# 05_INPUT.net
KiCad netlist of a schematic drawn in Altium Designer
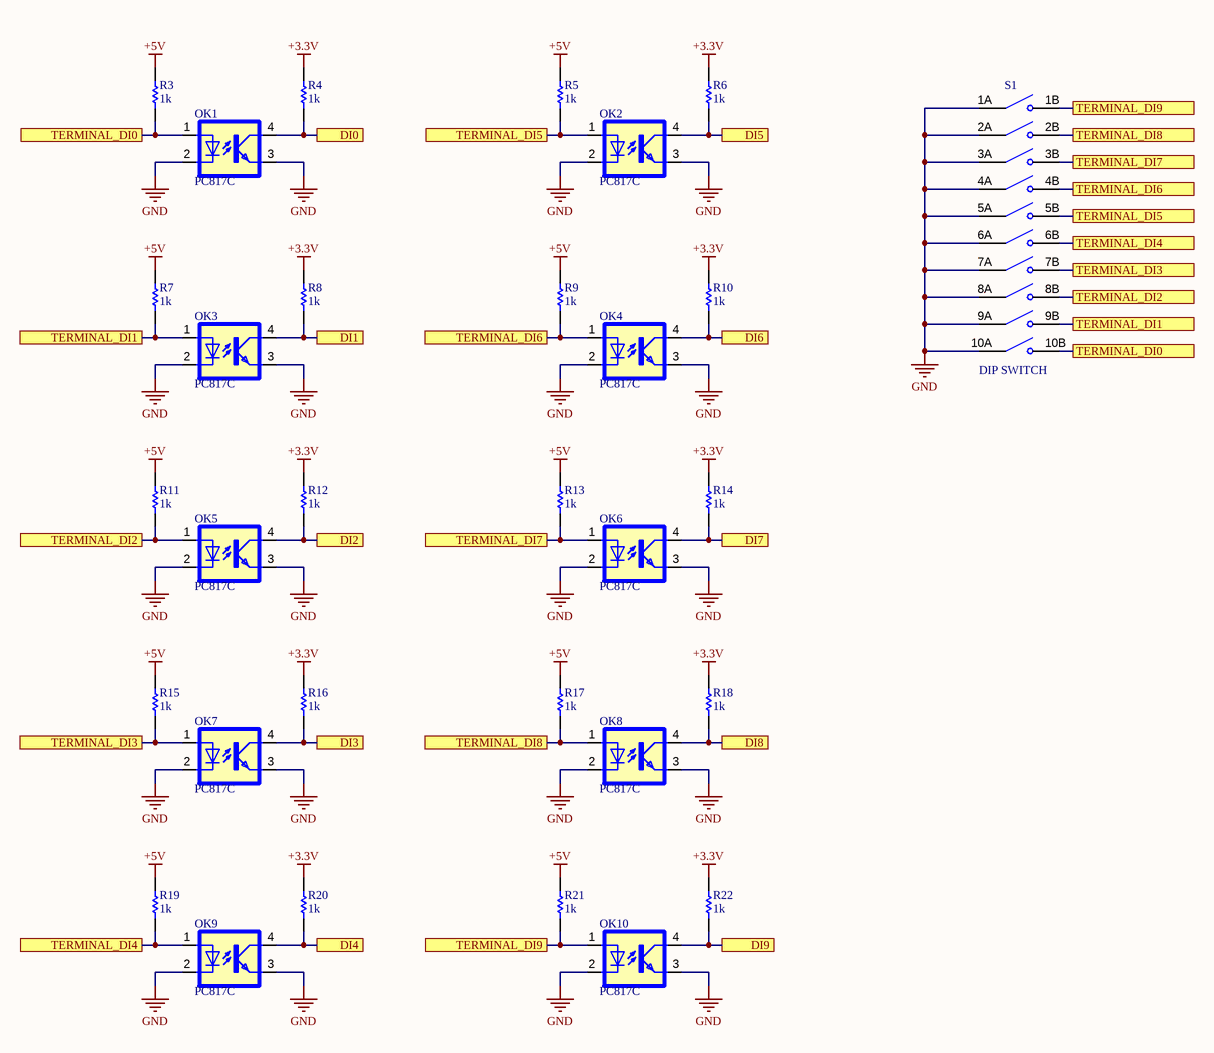
[diagram p0: 05_INPUT.SchDoc]

(export (version "E")
  (design (tool "Eeschema 10.0.6"))
  (components
    (comp (ref "OK1")
      (value "PC817C")
      (footprint "SOP254P975X460-4N")
      (description "RF Mixer IC Cellular, DCS, PCS, W-CDMA, WLAN Up Converter 50MHz ~ 400MHz 6-SuperMiniMold")
      (fields (field (name "MF") "Renesas Electronics America Inc") (field (name "MP") "PC817"))
      (libsource (lib "PROC051C_AWR1843BOOST_RevC") (part "PC817C"))
    )
    (comp (ref "OK2")
      (value "PC817C")
      (footprint "SOP254P975X460-4N")
      (description "RF Mixer IC Cellular, DCS, PCS, W-CDMA, WLAN Up Converter 50MHz ~ 400MHz 6-SuperMiniMold")
      (fields (field (name "MF") "Renesas Electronics America Inc") (field (name "MP") "PC817"))
      (libsource (lib "PROC051C_AWR1843BOOST_RevC") (part "PC817C"))
    )
    (comp (ref "OK3")
      (value "PC817C")
      (footprint "SOP254P975X460-4N")
      (description "RF Mixer IC Cellular, DCS, PCS, W-CDMA, WLAN Up Converter 50MHz ~ 400MHz 6-SuperMiniMold")
      (fields (field (name "MF") "Renesas Electronics America Inc") (field (name "MP") "PC817"))
      (libsource (lib "PROC051C_AWR1843BOOST_RevC") (part "PC817C"))
    )
    (comp (ref "OK4")
      (value "PC817C")
      (footprint "SOP254P975X460-4N")
      (description "RF Mixer IC Cellular, DCS, PCS, W-CDMA, WLAN Up Converter 50MHz ~ 400MHz 6-SuperMiniMold")
      (fields (field (name "MF") "Renesas Electronics America Inc") (field (name "MP") "PC817"))
      (libsource (lib "PROC051C_AWR1843BOOST_RevC") (part "PC817C"))
    )
    (comp (ref "OK5")
      (value "PC817C")
      (footprint "SOP254P975X460-4N")
      (description "RF Mixer IC Cellular, DCS, PCS, W-CDMA, WLAN Up Converter 50MHz ~ 400MHz 6-SuperMiniMold")
      (fields (field (name "MF") "Renesas Electronics America Inc") (field (name "MP") "PC817"))
      (libsource (lib "PROC051C_AWR1843BOOST_RevC") (part "PC817C"))
    )
    (comp (ref "OK6")
      (value "PC817C")
      (footprint "SOP254P975X460-4N")
      (description "RF Mixer IC Cellular, DCS, PCS, W-CDMA, WLAN Up Converter 50MHz ~ 400MHz 6-SuperMiniMold")
      (fields (field (name "MF") "Renesas Electronics America Inc") (field (name "MP") "PC817"))
      (libsource (lib "PROC051C_AWR1843BOOST_RevC") (part "PC817C"))
    )
    (comp (ref "OK7")
      (value "PC817C")
      (footprint "SOP254P975X460-4N")
      (description "RF Mixer IC Cellular, DCS, PCS, W-CDMA, WLAN Up Converter 50MHz ~ 400MHz 6-SuperMiniMold")
      (fields (field (name "MF") "Renesas Electronics America Inc") (field (name "MP") "PC817"))
      (libsource (lib "PROC051C_AWR1843BOOST_RevC") (part "PC817C"))
    )
    (comp (ref "OK8")
      (value "PC817C")
      (footprint "SOP254P975X460-4N")
      (description "RF Mixer IC Cellular, DCS, PCS, W-CDMA, WLAN Up Converter 50MHz ~ 400MHz 6-SuperMiniMold")
      (fields (field (name "MF") "Renesas Electronics America Inc") (field (name "MP") "PC817"))
      (libsource (lib "PROC051C_AWR1843BOOST_RevC") (part "PC817C"))
    )
    (comp (ref "OK9")
      (value "PC817C")
      (footprint "SOP254P975X460-4N")
      (description "RF Mixer IC Cellular, DCS, PCS, W-CDMA, WLAN Up Converter 50MHz ~ 400MHz 6-SuperMiniMold")
      (fields (field (name "MF") "Renesas Electronics America Inc") (field (name "MP") "PC817"))
      (libsource (lib "PROC051C_AWR1843BOOST_RevC") (part "PC817C"))
    )
    (comp (ref "OK10")
      (value "PC817C")
      (footprint "SOP254P975X460-4N")
      (description "RF Mixer IC Cellular, DCS, PCS, W-CDMA, WLAN Up Converter 50MHz ~ 400MHz 6-SuperMiniMold")
      (fields (field (name "MF") "Renesas Electronics America Inc") (field (name "MP") "PC817"))
      (libsource (lib "PROC051C_AWR1843BOOST_RevC") (part "PC817C"))
    )
    (comp (ref "R3")
      (value "RES 1.5K 0603")
      (footprint "0603")
      (description "RES, 1.5K, 1%, 0.1 W, AEC-Q200 Grade 0, 0603")
      (fields
        (field (name "MANUFACTURER") "Vishay-Dale")
        (field (name "PARTNUMBER") "CRCW060320R0JNEA")
        (field (name "VALUEDISPLAYED") "1k")
      )
      (libsource (lib "PROC051C_AWR1843BOOST_RevC") (part "RES 1.5K 0603 1%"))
    )
    (comp (ref "R4")
      (value "RES 1.5K 0603")
      (footprint "0603")
      (description "RES, 1.5K, 1%, 0.1 W, AEC-Q200 Grade 0, 0603")
      (fields
        (field (name "MANUFACTURER") "Vishay-Dale")
        (field (name "PARTNUMBER") "CRCW060320R0JNEA")
        (field (name "VALUEDISPLAYED") "1k")
      )
      (libsource (lib "PROC051C_AWR1843BOOST_RevC") (part "RES 1.5K 0603 1%"))
    )
    (comp (ref "R5")
      (value "RES 1.5K 0603")
      (footprint "0603")
      (description "RES, 1.5K, 1%, 0.1 W, AEC-Q200 Grade 0, 0603")
      (fields
        (field (name "MANUFACTURER") "Vishay-Dale")
        (field (name "PARTNUMBER") "CRCW060320R0JNEA")
        (field (name "VALUEDISPLAYED") "1k")
      )
      (libsource (lib "PROC051C_AWR1843BOOST_RevC") (part "RES 1.5K 0603 1%"))
    )
    (comp (ref "R6")
      (value "RES 1.5K 0603")
      (footprint "0603")
      (description "RES, 1.5K, 1%, 0.1 W, AEC-Q200 Grade 0, 0603")
      (fields
        (field (name "MANUFACTURER") "Vishay-Dale")
        (field (name "PARTNUMBER") "CRCW060320R0JNEA")
        (field (name "VALUEDISPLAYED") "1k")
      )
      (libsource (lib "PROC051C_AWR1843BOOST_RevC") (part "RES 1.5K 0603 1%"))
    )
    (comp (ref "R7")
      (value "RES 1.5K 0603")
      (footprint "0603")
      (description "RES, 1.5K, 1%, 0.1 W, AEC-Q200 Grade 0, 0603")
      (fields
        (field (name "MANUFACTURER") "Vishay-Dale")
        (field (name "PARTNUMBER") "CRCW060320R0JNEA")
        (field (name "VALUEDISPLAYED") "1k")
      )
      (libsource (lib "PROC051C_AWR1843BOOST_RevC") (part "RES 1.5K 0603 1%"))
    )
    (comp (ref "R8")
      (value "RES 1.5K 0603")
      (footprint "0603")
      (description "RES, 1.5K, 1%, 0.1 W, AEC-Q200 Grade 0, 0603")
      (fields
        (field (name "MANUFACTURER") "Vishay-Dale")
        (field (name "PARTNUMBER") "CRCW060320R0JNEA")
        (field (name "VALUEDISPLAYED") "1k")
      )
      (libsource (lib "PROC051C_AWR1843BOOST_RevC") (part "RES 1.5K 0603 1%"))
    )
    (comp (ref "R9")
      (value "RES 1.5K 0603")
      (footprint "0603")
      (description "RES, 1.5K, 1%, 0.1 W, AEC-Q200 Grade 0, 0603")
      (fields
        (field (name "MANUFACTURER") "Vishay-Dale")
        (field (name "PARTNUMBER") "CRCW060320R0JNEA")
        (field (name "VALUEDISPLAYED") "1k")
      )
      (libsource (lib "PROC051C_AWR1843BOOST_RevC") (part "RES 1.5K 0603 1%"))
    )
    (comp (ref "R10")
      (value "RES 1.5K 0603")
      (footprint "0603")
      (description "RES, 1.5K, 1%, 0.1 W, AEC-Q200 Grade 0, 0603")
      (fields
        (field (name "MANUFACTURER") "Vishay-Dale")
        (field (name "PARTNUMBER") "CRCW060320R0JNEA")
        (field (name "VALUEDISPLAYED") "1k")
      )
      (libsource (lib "PROC051C_AWR1843BOOST_RevC") (part "RES 1.5K 0603 1%"))
    )
    (comp (ref "R11")
      (value "RES 1.5K 0603")
      (footprint "0603")
      (description "RES, 1.5K, 1%, 0.1 W, AEC-Q200 Grade 0, 0603")
      (fields
        (field (name "MANUFACTURER") "Vishay-Dale")
        (field (name "PARTNUMBER") "CRCW060320R0JNEA")
        (field (name "VALUEDISPLAYED") "1k")
      )
      (libsource (lib "PROC051C_AWR1843BOOST_RevC") (part "RES 1.5K 0603 1%"))
    )
    (comp (ref "R12")
      (value "RES 1.5K 0603")
      (footprint "0603")
      (description "RES, 1.5K, 1%, 0.1 W, AEC-Q200 Grade 0, 0603")
      (fields
        (field (name "MANUFACTURER") "Vishay-Dale")
        (field (name "PARTNUMBER") "CRCW060320R0JNEA")
        (field (name "VALUEDISPLAYED") "1k")
      )
      (libsource (lib "PROC051C_AWR1843BOOST_RevC") (part "RES 1.5K 0603 1%"))
    )
    (comp (ref "R13")
      (value "RES 1.5K 0603")
      (footprint "0603")
      (description "RES, 1.5K, 1%, 0.1 W, AEC-Q200 Grade 0, 0603")
      (fields
        (field (name "MANUFACTURER") "Vishay-Dale")
        (field (name "PARTNUMBER") "CRCW060320R0JNEA")
        (field (name "VALUEDISPLAYED") "1k")
      )
      (libsource (lib "PROC051C_AWR1843BOOST_RevC") (part "RES 1.5K 0603 1%"))
    )
    (comp (ref "R14")
      (value "RES 1.5K 0603")
      (footprint "0603")
      (description "RES, 1.5K, 1%, 0.1 W, AEC-Q200 Grade 0, 0603")
      (fields
        (field (name "MANUFACTURER") "Vishay-Dale")
        (field (name "PARTNUMBER") "CRCW060320R0JNEA")
        (field (name "VALUEDISPLAYED") "1k")
      )
      (libsource (lib "PROC051C_AWR1843BOOST_RevC") (part "RES 1.5K 0603 1%"))
    )
    (comp (ref "R15")
      (value "RES 1.5K 0603")
      (footprint "0603")
      (description "RES, 1.5K, 1%, 0.1 W, AEC-Q200 Grade 0, 0603")
      (fields
        (field (name "MANUFACTURER") "Vishay-Dale")
        (field (name "PARTNUMBER") "CRCW060320R0JNEA")
        (field (name "VALUEDISPLAYED") "1k")
      )
      (libsource (lib "PROC051C_AWR1843BOOST_RevC") (part "RES 1.5K 0603 1%"))
    )
    (comp (ref "R16")
      (value "RES 1.5K 0603")
      (footprint "0603")
      (description "RES, 1.5K, 1%, 0.1 W, AEC-Q200 Grade 0, 0603")
      (fields
        (field (name "MANUFACTURER") "Vishay-Dale")
        (field (name "PARTNUMBER") "CRCW060320R0JNEA")
        (field (name "VALUEDISPLAYED") "1k")
      )
      (libsource (lib "PROC051C_AWR1843BOOST_RevC") (part "RES 1.5K 0603 1%"))
    )
    (comp (ref "R17")
      (value "RES 1.5K 0603")
      (footprint "0603")
      (description "RES, 1.5K, 1%, 0.1 W, AEC-Q200 Grade 0, 0603")
      (fields
        (field (name "MANUFACTURER") "Vishay-Dale")
        (field (name "PARTNUMBER") "CRCW060320R0JNEA")
        (field (name "VALUEDISPLAYED") "1k")
      )
      (libsource (lib "PROC051C_AWR1843BOOST_RevC") (part "RES 1.5K 0603 1%"))
    )
    (comp (ref "R18")
      (value "RES 1.5K 0603")
      (footprint "0603")
      (description "RES, 1.5K, 1%, 0.1 W, AEC-Q200 Grade 0, 0603")
      (fields
        (field (name "MANUFACTURER") "Vishay-Dale")
        (field (name "PARTNUMBER") "CRCW060320R0JNEA")
        (field (name "VALUEDISPLAYED") "1k")
      )
      (libsource (lib "PROC051C_AWR1843BOOST_RevC") (part "RES 1.5K 0603 1%"))
    )
    (comp (ref "R19")
      (value "RES 1.5K 0603")
      (footprint "0603")
      (description "RES, 1.5K, 1%, 0.1 W, AEC-Q200 Grade 0, 0603")
      (fields
        (field (name "MANUFACTURER") "Vishay-Dale")
        (field (name "PARTNUMBER") "CRCW060320R0JNEA")
        (field (name "VALUEDISPLAYED") "1k")
      )
      (libsource (lib "PROC051C_AWR1843BOOST_RevC") (part "RES 1.5K 0603 1%"))
    )
    (comp (ref "R20")
      (value "RES 1.5K 0603")
      (footprint "0603")
      (description "RES, 1.5K, 1%, 0.1 W, AEC-Q200 Grade 0, 0603")
      (fields
        (field (name "MANUFACTURER") "Vishay-Dale")
        (field (name "PARTNUMBER") "CRCW060320R0JNEA")
        (field (name "VALUEDISPLAYED") "1k")
      )
      (libsource (lib "PROC051C_AWR1843BOOST_RevC") (part "RES 1.5K 0603 1%"))
    )
    (comp (ref "R21")
      (value "RES 1.5K 0603")
      (footprint "0603")
      (description "RES, 1.5K, 1%, 0.1 W, AEC-Q200 Grade 0, 0603")
      (fields
        (field (name "MANUFACTURER") "Vishay-Dale")
        (field (name "PARTNUMBER") "CRCW060320R0JNEA")
        (field (name "VALUEDISPLAYED") "1k")
      )
      (libsource (lib "PROC051C_AWR1843BOOST_RevC") (part "RES 1.5K 0603 1%"))
    )
    (comp (ref "R22")
      (value "RES 1.5K 0603")
      (footprint "0603")
      (description "RES, 1.5K, 1%, 0.1 W, AEC-Q200 Grade 0, 0603")
      (fields
        (field (name "MANUFACTURER") "Vishay-Dale")
        (field (name "PARTNUMBER") "CRCW060320R0JNEA")
        (field (name "VALUEDISPLAYED") "1k")
      )
      (libsource (lib "PROC051C_AWR1843BOOST_RevC") (part "RES 1.5K 0603 1%"))
    )
    (comp (ref "S1")
      (value "DIP SWITCH")
      (footprint "SW_DS01-254-L-10BE")
      (description "10 Position, Through Hole, 2.54 mm Pitch, Raised Slide Actuator, Flat Bottom, Long Pin, DIP Switch")
      (fields (field (name "MF") "Same Sky") (field (name "MP") "DS01-254-L-10BE"))
      (libsource (lib "PROC051C_AWR1843BOOST_RevC") (part "DS01-254-L-10BE"))
    )
  )
  (nets
    (net (code "1") (name "+3.3V") (class "Default")
      (node (ref "R10") (pin "2") (pinfunction "2_2") (pintype "passive"))
      (node (ref "R12") (pin "2") (pinfunction "2_2") (pintype "passive"))
      (node (ref "R14") (pin "2") (pinfunction "2_2") (pintype "passive"))
      (node (ref "R16") (pin "2") (pinfunction "2_2") (pintype "passive"))
      (node (ref "R18") (pin "2") (pinfunction "2_2") (pintype "passive"))
      (node (ref "R20") (pin "2") (pinfunction "2_2") (pintype "passive"))
      (node (ref "R22") (pin "2") (pinfunction "2_2") (pintype "passive"))
      (node (ref "R4") (pin "2") (pinfunction "2_2") (pintype "passive"))
      (node (ref "R6") (pin "2") (pinfunction "2_2") (pintype "passive"))
      (node (ref "R8") (pin "2") (pinfunction "2_2") (pintype "passive"))
    )
    (net (code "2") (name "+5V") (class "Default")
      (node (ref "R11") (pin "2") (pinfunction "2_2") (pintype "passive"))
      (node (ref "R13") (pin "2") (pinfunction "2_2") (pintype "passive"))
      (node (ref "R15") (pin "2") (pinfunction "2_2") (pintype "passive"))
      (node (ref "R17") (pin "2") (pinfunction "2_2") (pintype "passive"))
      (node (ref "R19") (pin "2") (pinfunction "2_2") (pintype "passive"))
      (node (ref "R21") (pin "2") (pinfunction "2_2") (pintype "passive"))
      (node (ref "R3") (pin "2") (pinfunction "2_2") (pintype "passive"))
      (node (ref "R5") (pin "2") (pinfunction "2_2") (pintype "passive"))
      (node (ref "R7") (pin "2") (pinfunction "2_2") (pintype "passive"))
      (node (ref "R9") (pin "2") (pinfunction "2_2") (pintype "passive"))
    )
    (net (code "3") (name "/DI0") (class "Default")
      (node (ref "OK1") (pin "4") (pinfunction "COL_4") (pintype "passive"))
      (node (ref "R4") (pin "1") (pinfunction "1_1") (pintype "passive"))
    )
    (net (code "4") (name "/DI1") (class "Default")
      (node (ref "OK3") (pin "4") (pinfunction "COL_4") (pintype "passive"))
      (node (ref "R8") (pin "1") (pinfunction "1_1") (pintype "passive"))
    )
    (net (code "5") (name "/DI2") (class "Default")
      (node (ref "OK5") (pin "4") (pinfunction "COL_4") (pintype "passive"))
      (node (ref "R12") (pin "1") (pinfunction "1_1") (pintype "passive"))
    )
    (net (code "6") (name "/DI3") (class "Default")
      (node (ref "OK7") (pin "4") (pinfunction "COL_4") (pintype "passive"))
      (node (ref "R16") (pin "1") (pinfunction "1_1") (pintype "passive"))
    )
    (net (code "7") (name "/DI4") (class "Default")
      (node (ref "OK9") (pin "4") (pinfunction "COL_4") (pintype "passive"))
      (node (ref "R20") (pin "1") (pinfunction "1_1") (pintype "passive"))
    )
    (net (code "8") (name "/DI5") (class "Default")
      (node (ref "OK2") (pin "4") (pinfunction "COL_4") (pintype "passive"))
      (node (ref "R6") (pin "1") (pinfunction "1_1") (pintype "passive"))
    )
    (net (code "9") (name "/DI6") (class "Default")
      (node (ref "OK4") (pin "4") (pinfunction "COL_4") (pintype "passive"))
      (node (ref "R10") (pin "1") (pinfunction "1_1") (pintype "passive"))
    )
    (net (code "10") (name "/DI7") (class "Default")
      (node (ref "OK6") (pin "4") (pinfunction "COL_4") (pintype "passive"))
      (node (ref "R14") (pin "1") (pinfunction "1_1") (pintype "passive"))
    )
    (net (code "11") (name "/DI8") (class "Default")
      (node (ref "OK8") (pin "4") (pinfunction "COL_4") (pintype "passive"))
      (node (ref "R18") (pin "1") (pinfunction "1_1") (pintype "passive"))
    )
    (net (code "12") (name "/DI9") (class "Default")
      (node (ref "OK10") (pin "4") (pinfunction "COL_4") (pintype "passive"))
      (node (ref "R22") (pin "1") (pinfunction "1_1") (pintype "passive"))
    )
    (net (code "13") (name "/TERMINAL_DI0") (class "Default")
      (node (ref "OK1") (pin "1") (pinfunction "A_1") (pintype "passive"))
      (node (ref "R3") (pin "1") (pinfunction "1_1") (pintype "passive"))
      (node (ref "S1") (pin "10B") (pinfunction "NO10_10B") (pintype "passive"))
    )
    (net (code "14") (name "/TERMINAL_DI1") (class "Default")
      (node (ref "OK3") (pin "1") (pinfunction "A_1") (pintype "passive"))
      (node (ref "R7") (pin "1") (pinfunction "1_1") (pintype "passive"))
      (node (ref "S1") (pin "9B") (pinfunction "NO9_9B") (pintype "passive"))
    )
    (net (code "15") (name "/TERMINAL_DI2") (class "Default")
      (node (ref "OK5") (pin "1") (pinfunction "A_1") (pintype "passive"))
      (node (ref "R11") (pin "1") (pinfunction "1_1") (pintype "passive"))
      (node (ref "S1") (pin "8B") (pinfunction "NO8_8B") (pintype "passive"))
    )
    (net (code "16") (name "/TERMINAL_DI3") (class "Default")
      (node (ref "OK7") (pin "1") (pinfunction "A_1") (pintype "passive"))
      (node (ref "R15") (pin "1") (pinfunction "1_1") (pintype "passive"))
      (node (ref "S1") (pin "7B") (pinfunction "NO7_7B") (pintype "passive"))
    )
    (net (code "17") (name "/TERMINAL_DI4") (class "Default")
      (node (ref "OK9") (pin "1") (pinfunction "A_1") (pintype "passive"))
      (node (ref "R19") (pin "1") (pinfunction "1_1") (pintype "passive"))
      (node (ref "S1") (pin "6B") (pinfunction "NO6_6B") (pintype "passive"))
    )
    (net (code "18") (name "/TERMINAL_DI5") (class "Default")
      (node (ref "OK2") (pin "1") (pinfunction "A_1") (pintype "passive"))
      (node (ref "R5") (pin "1") (pinfunction "1_1") (pintype "passive"))
      (node (ref "S1") (pin "5B") (pinfunction "NO5_5B") (pintype "passive"))
    )
    (net (code "19") (name "/TERMINAL_DI6") (class "Default")
      (node (ref "OK4") (pin "1") (pinfunction "A_1") (pintype "passive"))
      (node (ref "R9") (pin "1") (pinfunction "1_1") (pintype "passive"))
      (node (ref "S1") (pin "4B") (pinfunction "NO4_4B") (pintype "passive"))
    )
    (net (code "20") (name "/TERMINAL_DI7") (class "Default")
      (node (ref "OK6") (pin "1") (pinfunction "A_1") (pintype "passive"))
      (node (ref "R13") (pin "1") (pinfunction "1_1") (pintype "passive"))
      (node (ref "S1") (pin "3B") (pinfunction "NO3_3B") (pintype "passive"))
    )
    (net (code "21") (name "/TERMINAL_DI8") (class "Default")
      (node (ref "OK8") (pin "1") (pinfunction "A_1") (pintype "passive"))
      (node (ref "R17") (pin "1") (pinfunction "1_1") (pintype "passive"))
      (node (ref "S1") (pin "2B") (pinfunction "NO2_2B") (pintype "passive"))
    )
    (net (code "22") (name "/TERMINAL_DI9") (class "Default")
      (node (ref "OK10") (pin "1") (pinfunction "A_1") (pintype "passive"))
      (node (ref "R21") (pin "1") (pinfunction "1_1") (pintype "passive"))
      (node (ref "S1") (pin "1B") (pinfunction "NO1_1B") (pintype "passive"))
    )
    (net (code "23") (name "GND") (class "Default")
      (node (ref "OK1") (pin "2") (pinfunction "C_2") (pintype "passive"))
      (node (ref "OK1") (pin "3") (pinfunction "EMIT_3") (pintype "passive"))
      (node (ref "OK10") (pin "2") (pinfunction "C_2") (pintype "passive"))
      (node (ref "OK10") (pin "3") (pinfunction "EMIT_3") (pintype "passive"))
      (node (ref "OK2") (pin "2") (pinfunction "C_2") (pintype "passive"))
      (node (ref "OK2") (pin "3") (pinfunction "EMIT_3") (pintype "passive"))
      (node (ref "OK3") (pin "2") (pinfunction "C_2") (pintype "passive"))
      (node (ref "OK3") (pin "3") (pinfunction "EMIT_3") (pintype "passive"))
      (node (ref "OK4") (pin "2") (pinfunction "C_2") (pintype "passive"))
      (node (ref "OK4") (pin "3") (pinfunction "EMIT_3") (pintype "passive"))
      (node (ref "OK5") (pin "2") (pinfunction "C_2") (pintype "passive"))
      (node (ref "OK5") (pin "3") (pinfunction "EMIT_3") (pintype "passive"))
      (node (ref "OK6") (pin "2") (pinfunction "C_2") (pintype "passive"))
      (node (ref "OK6") (pin "3") (pinfunction "EMIT_3") (pintype "passive"))
      (node (ref "OK7") (pin "2") (pinfunction "C_2") (pintype "passive"))
      (node (ref "OK7") (pin "3") (pinfunction "EMIT_3") (pintype "passive"))
      (node (ref "OK8") (pin "2") (pinfunction "C_2") (pintype "passive"))
      (node (ref "OK8") (pin "3") (pinfunction "EMIT_3") (pintype "passive"))
      (node (ref "OK9") (pin "2") (pinfunction "C_2") (pintype "passive"))
      (node (ref "OK9") (pin "3") (pinfunction "EMIT_3") (pintype "passive"))
      (node (ref "S1") (pin "10A") (pinfunction "COM10_10A") (pintype "passive"))
      (node (ref "S1") (pin "1A") (pinfunction "COM1_1A") (pintype "passive"))
      (node (ref "S1") (pin "2A") (pinfunction "COM2_2A") (pintype "passive"))
      (node (ref "S1") (pin "3A") (pinfunction "COM3_3A") (pintype "passive"))
      (node (ref "S1") (pin "4A") (pinfunction "COM4_4A") (pintype "passive"))
      (node (ref "S1") (pin "5A") (pinfunction "COM5_5A") (pintype "passive"))
      (node (ref "S1") (pin "6A") (pinfunction "COM6_6A") (pintype "passive"))
      (node (ref "S1") (pin "7A") (pinfunction "COM7_7A") (pintype "passive"))
      (node (ref "S1") (pin "8A") (pinfunction "COM8_8A") (pintype "passive"))
      (node (ref "S1") (pin "9A") (pinfunction "COM9_9A") (pintype "passive"))
    )
  )
)
